# 2025-11-30_13-06-011.net
KiCad netlist of a schematic drawn in Altium Designer
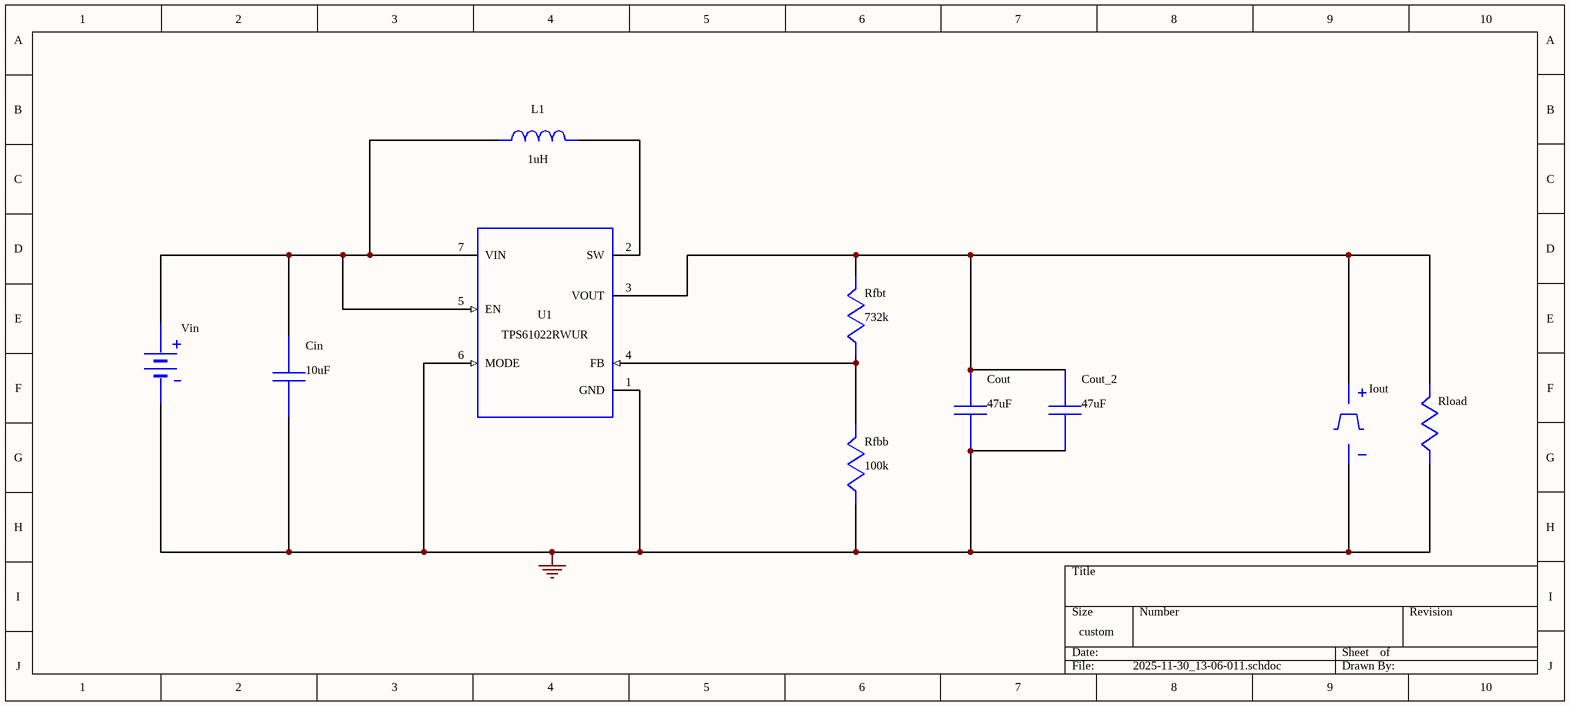
[diagram p0: 2025-11-30_13-06-011.schdoc]

(export (version "E")
  (design (tool "Eeschema 10.0.6"))
  (components
    (comp (ref "Cin")
      (value "10uF")
      (description "C0805C106K8PACTU")
      (libsource (lib "TI WEBENCH") (part "Cin"))
    )
    (comp (ref "Cout")
      (value "47uF")
      (description "GRM31CR61A476KE1")
      (fields (field (name "MANUFACTURER PART NUMBER") "GRM31CR61A476KE15L"))
      (libsource (lib "TI WEBENCH") (part "Cout"))
    )
    (comp (ref "Cout_2")
      (value "47uF")
      (description "GRM31CR61A476KE1")
      (fields (field (name "MANUFACTURER PART NUMBER") "GRM31CR61A476KE15L"))
      (libsource (lib "TI WEBENCH") (part "Cout_2"))
    )
    (comp (ref "Iout")
      (value "WB_PWL_CURRENT_LOAD")
      (description "WB_PWL_CURRENT_L")
      (libsource (lib "TI WEBENCH") (part "Iout"))
    )
    (comp (ref "L1") (value "1uH") (description "XAL4020-102MEB") (libsource (lib "TI WEBENCH") (part "L1")))
    (comp (ref "Rfbb")
      (value "100k")
      (description "CRCW0402100KFKED")
      (libsource (lib "TI WEBENCH") (part "Rfbb"))
    )
    (comp (ref "Rfbt")
      (value "732k")
      (description "CRCW0402732KFKED")
      (libsource (lib "TI WEBENCH") (part "Rfbt"))
    )
    (comp (ref "Rload") (value "WB_LOAD_RESISTOR") (libsource (lib "TI WEBENCH") (part "Rload")))
    (comp (ref "U1")
      (value "TPS61022RWUR")
      (fields (field (name "PACKAGEREFERENCE") "TPS61022RWUR"))
      (libsource (lib "TI WEBENCH") (part "U1"))
    )
    (comp (ref "Vin") (value "WB_BATTERY") (libsource (lib "TI WEBENCH") (part "Vin")))
  )
  (nets
    (net (code "1") (name "0") (class "Default")
      (node (ref "Cin") (pin "2") (pinfunction "2_2") (pintype "passive"))
      (node (ref "Cout") (pin "2") (pinfunction "2_2") (pintype "passive"))
      (node (ref "Cout_2") (pin "2") (pinfunction "2_2") (pintype "passive"))
      (node (ref "Iout") (pin "2") (pinfunction "-_2") (pintype "passive"))
      (node (ref "Rfbb") (pin "2") (pinfunction "2_2") (pintype "passive"))
      (node (ref "Rload") (pin "2") (pinfunction "2_2") (pintype "passive"))
      (node (ref "U1") (pin "1") (pinfunction "GND_1") (pintype "power_in"))
      (node (ref "U1") (pin "6") (pinfunction "MODE_6") (pintype "input"))
      (node (ref "Vin") (pin "2") (pinfunction "-_2") (pintype "passive"))
    )
    (net (code "2") (name "Net-(Iout-+)") (class "Default")
      (node (ref "Cout") (pin "1") (pinfunction "1_1") (pintype "passive"))
      (node (ref "Cout_2") (pin "1") (pinfunction "1_1") (pintype "passive"))
      (node (ref "Iout") (pin "1") (pinfunction "+_1") (pintype "passive"))
      (node (ref "Rfbt") (pin "1") (pinfunction "1_1") (pintype "passive"))
      (node (ref "Rload") (pin "1") (pinfunction "1_1") (pintype "passive"))
      (node (ref "U1") (pin "3") (pinfunction "VOUT_3") (pintype "power_in"))
    )
    (net (code "3") (name "Net-(U1-EN)") (class "Default")
      (node (ref "Cin") (pin "1") (pinfunction "1_1") (pintype "passive"))
      (node (ref "L1") (pin "1") (pinfunction "1_1") (pintype "passive"))
      (node (ref "U1") (pin "5") (pinfunction "EN_5") (pintype "input"))
      (node (ref "U1") (pin "7") (pinfunction "VIN_7") (pintype "power_in"))
      (node (ref "Vin") (pin "1") (pinfunction "+_1") (pintype "passive"))
    )
    (net (code "4") (name "Net-(U1-FB)") (class "Default")
      (node (ref "Rfbb") (pin "1") (pinfunction "1_1") (pintype "passive"))
      (node (ref "Rfbt") (pin "2") (pinfunction "2_2") (pintype "passive"))
      (node (ref "U1") (pin "4") (pinfunction "FB_4") (pintype "input"))
    )
    (net (code "5") (name "Net-(U1-SW)") (class "Default")
      (node (ref "L1") (pin "2") (pinfunction "2_2") (pintype "passive"))
      (node (ref "U1") (pin "2") (pinfunction "SW_2") (pintype "power_in"))
    )
  )
)
